# Ethernet.net
KiCad netlist of a schematic drawn in Altium Designer
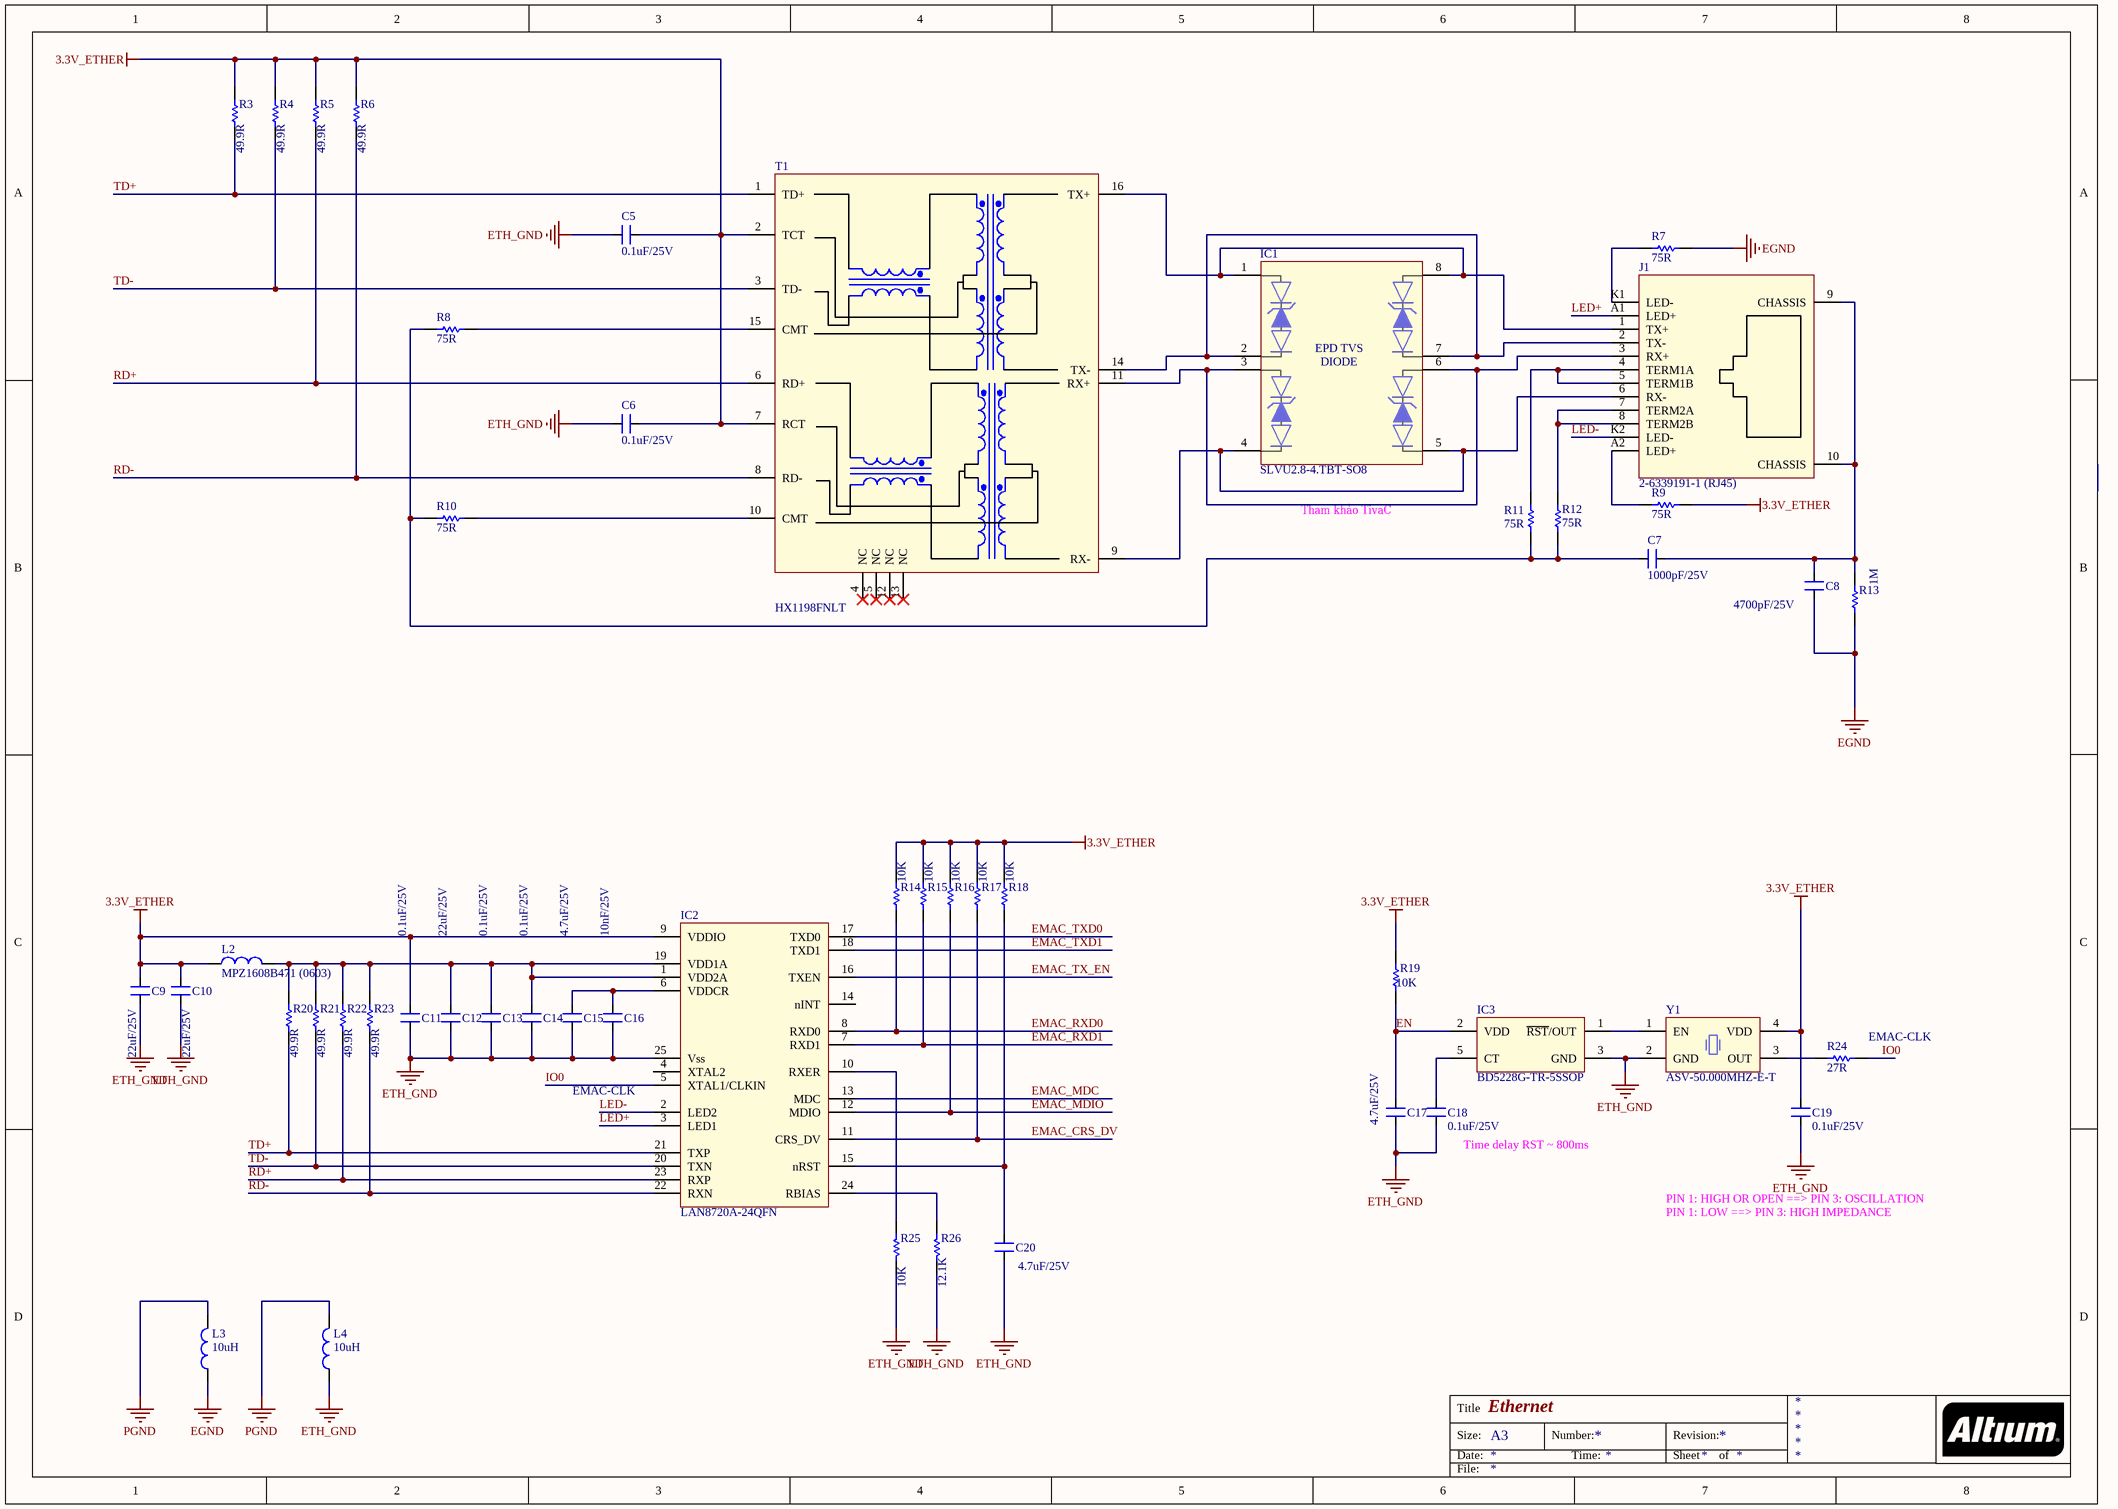
[diagram p0: Ethernet.SchDoc]

(export (version "E")
  (design (tool "Eeschema 10.0.6"))
  (components
    (comp (ref "C5")
      (value "0.1uF/25V")
      (footprint "CAP_CERA_C2012(CC0805INCH)")
      (description "0.1µF ±10% 25V Ceramic Capacitor X7R 0805 (2012 Metric)")
      (libsource (lib "lpson") (part "CAP CERA 0805"))
    )
    (comp (ref "C6")
      (value "0.1uF/25V")
      (footprint "CAP_CERA_C2012(CC0805INCH)")
      (description "0.1µF ±10% 25V Ceramic Capacitor X7R 0805 (2012 Metric)")
      (libsource (lib "lpson") (part "CAP CERA 0805"))
    )
    (comp (ref "C7")
      (value "1000pF/25V")
      (footprint "CAP_CERA_C2012(CC0805INCH)")
      (description "1000pF ±10% 25V Ceramic Capacitor X7R 0805 (2012 Metric)")
      (libsource (lib "lpson") (part "CAP CERA 0805"))
    )
    (comp (ref "C8")
      (value "4700pF/25V")
      (footprint "CAP_CERA_C2012(CC0805INCH)")
      (description "4700pF ±10% 25V Ceramic Capacitor X7R 0805 (2012 Metric)")
      (libsource (lib "lpson") (part "CAP CERA 0805"))
    )
    (comp (ref "C9")
      (value "22uF/25V")
      (footprint "CAP_CERA_C2012(CC0805INCH)")
      (description "22µF ±20% 25V Ceramic Capacitor X5R 0805 (2012 Metric)")
      (libsource (lib "lpson") (part "CAP CERA 0805"))
    )
    (comp (ref "C10")
      (value "22uF/25V")
      (footprint "CAP_CERA_C2012(CC0805INCH)")
      (description "22µF ±20% 25V Ceramic Capacitor X5R 0805 (2012 Metric)")
      (libsource (lib "lpson") (part "CAP CERA 0805"))
    )
    (comp (ref "C11")
      (value "0.1uF/25V")
      (footprint "CAP_CERA_C2012(CC0805INCH)")
      (description "0.1µF ±10% 25V Ceramic Capacitor X7R 0805 (2012 Metric)")
      (libsource (lib "lpson") (part "CAP CERA 0805"))
    )
    (comp (ref "C12")
      (value "22uF/25V")
      (footprint "CAP_CERA_C2012(CC0805INCH)")
      (description "22µF ±20% 25V Ceramic Capacitor X5R 0805 (2012 Metric)")
      (libsource (lib "lpson") (part "CAP CERA 0805"))
    )
    (comp (ref "C13")
      (value "0.1uF/25V")
      (footprint "CAP_CERA_C2012(CC0805INCH)")
      (description "0.1µF ±10% 25V Ceramic Capacitor X7R 0805 (2012 Metric)")
      (libsource (lib "lpson") (part "CAP CERA 0805"))
    )
    (comp (ref "C14")
      (value "0.1uF/25V")
      (footprint "CAP_CERA_C2012(CC0805INCH)")
      (description "0.1µF ±10% 25V Ceramic Capacitor X7R 0805 (2012 Metric)")
      (libsource (lib "lpson") (part "CAP CERA 0805"))
    )
    (comp (ref "C15")
      (value "4.7uF/25V")
      (footprint "CAP_CERA_C2012(CC0805INCH)")
      (description "4.7µF ±10% 25V Ceramic Capacitor X5R 0805 (2012 Metric)")
      (libsource (lib "lpson") (part "CAP CERA 0805"))
    )
    (comp (ref "C16")
      (value "10nF/25V")
      (footprint "CAP_CERA_C2012(CC0805INCH)")
      (description "1nF=1000pF ±10% 25V Ceramic Capacitor X7R 0805 (2012 Metric)")
      (libsource (lib "lpson") (part "CAP CERA 0805"))
    )
    (comp (ref "C17")
      (value "4.7uF/25V")
      (footprint "CAP_CERA_C2012(CC0805INCH)")
      (description "4.7µF ±10% 25V Ceramic Capacitor X5R 0805 (2012 Metric)")
      (libsource (lib "lpson") (part "CAP CERA 0805"))
    )
    (comp (ref "C18")
      (value "0.1uF/25V")
      (footprint "CAP_CERA_C2012(CC0805INCH)")
      (description "0.1µF ±10% 25V Ceramic Capacitor X7R 0805 (2012 Metric)")
      (libsource (lib "lpson") (part "CAP CERA 0805"))
    )
    (comp (ref "C19")
      (value "0.1uF/25V")
      (footprint "CAP_CERA_C2012(CC0805INCH)")
      (description "0.1µF ±10% 25V Ceramic Capacitor X7R 0805 (2012 Metric)")
      (libsource (lib "lpson") (part "CAP CERA 0805"))
    )
    (comp (ref "C20")
      (value "4.7uF/25V")
      (footprint "CAP_CERA_C2012(CC0805INCH)")
      (description "4.7µF ±10% 25V Ceramic Capacitor X5R 0805 (2012 Metric)")
      (libsource (lib "lpson") (part "CAP CERA 0805"))
    )
    (comp (ref "IC1")
      (value "SLVU2.8-4.TBT-SO8")
      (footprint "SLVU2.8-4.TBT - 8S0")
      (description "TVS DIODE 2.8V 15V 8SO, EPD TVS Diode Array For ESD and Latch-Up Protection")
      (libsource (lib "lpson") (part "SLVU2.8-4.TBT"))
    )
    (comp (ref "IC2")
      (value "LAN8720A-24QFN")
      (footprint "LAN8720A 24QFN")
      (description "IC TXRX ETHERNET 24QFN,  2/2 Transceiver Full RMII 24-QFN (4x4)")
      (libsource (lib "lpson") (part "LAN8720A-24QFN"))
    )
    (comp (ref "IC3")
      (value "BD5228G-TR-5SSOP")
      (footprint "BD5228G -5SSOP")
      (description "IC DETECTOR VOLT 2.8V ODRN 5SSOP")
      (libsource (lib "lpson") (part "BD5228G-5SSOP"))
    )
    (comp (ref "J1")
      (value "2-6339191-1 (RJ45)")
      (footprint "RJ45-A121555CT-ND")
      (description "Jack Modular Connector 8p8c (RJ45, Ethernet) 90° Angle (Right) Shielded, EMI Finger Cat5")
      (libsource (lib "lpson") (part "RJ45-2-6339191-1"))
    )
    (comp (ref "L2")
      (value "MPZ1608B471 (0603)")
      (footprint "MPZ1608B471")
      (description "FERRITE BEAD 470 OHM 0603 1LN")
      (libsource (lib "lpson") (part "L1"))
    )
    (comp (ref "L3")
      (value "10uH")
      (footprint "L/0.4")
      (description "Inductor")
      (libsource (lib "lpson") (part "L1"))
    )
    (comp (ref "L4")
      (value "10uH")
      (footprint "L/0.4")
      (description "Inductor")
      (libsource (lib "lpson") (part "L1"))
    )
    (comp (ref "R3")
      (value "49.9R")
      (footprint "Res 0805 SMD")
      (description "49.9 Ohms ±1% 0.15W Chip Resistor 0805 (2012 Metric) Military Thick Film")
      (libsource (lib "lpson") (part "RES-0805"))
    )
    (comp (ref "R4")
      (value "49.9R")
      (footprint "Res 0805 SMD")
      (description "49.9 Ohms ±1% 0.15W Chip Resistor 0805 (2012 Metric) Military Thick Film")
      (libsource (lib "lpson") (part "RES-0805"))
    )
    (comp (ref "R5")
      (value "49.9R")
      (footprint "Res 0805 SMD")
      (description "49.9 Ohms ±1% 0.15W Chip Resistor 0805 (2012 Metric) Military Thick Film")
      (libsource (lib "lpson") (part "RES-0805"))
    )
    (comp (ref "R6")
      (value "49.9R")
      (footprint "Res 0805 SMD")
      (description "49.9 Ohms ±1% 0.15W Chip Resistor 0805 (2012 Metric) Military Thick Film")
      (libsource (lib "lpson") (part "RES-0805"))
    )
    (comp (ref "R7")
      (value "75R")
      (footprint "Res 0805 SMD")
      (description "75 Ohms ±1% 0.125W, 1/8W Chip Resistor 0805 (2012 Metric) Automotive AEC-Q200 Thick Film")
      (libsource (lib "lpson") (part "RES-0805"))
    )
    (comp (ref "R8")
      (value "75R")
      (footprint "Res 0805 SMD")
      (description "75 Ohms ±1% 0.125W, 1/8W Chip Resistor 0805 (2012 Metric) Automotive AEC-Q200 Thick Film")
      (libsource (lib "lpson") (part "RES-0805"))
    )
    (comp (ref "R9")
      (value "75R")
      (footprint "Res 0805 SMD")
      (description "75 Ohms ±1% 0.125W, 1/8W Chip Resistor 0805 (2012 Metric) Automotive AEC-Q200 Thick Film")
      (libsource (lib "lpson") (part "RES-0805"))
    )
    (comp (ref "R10")
      (value "75R")
      (footprint "Res 0805 SMD")
      (description "75 Ohms ±1% 0.125W, 1/8W Chip Resistor 0805 (2012 Metric) Automotive AEC-Q200 Thick Film")
      (libsource (lib "lpson") (part "RES-0805"))
    )
    (comp (ref "R11")
      (value "75R")
      (footprint "Res 0805 SMD")
      (description "75 Ohms ±1% 0.125W, 1/8W Chip Resistor 0805 (2012 Metric) Automotive AEC-Q200 Thick Film")
      (libsource (lib "lpson") (part "RES-0805"))
    )
    (comp (ref "R12")
      (value "75R")
      (footprint "Res 0805 SMD")
      (description "75 Ohms ±1% 0.125W, 1/8W Chip Resistor 0805 (2012 Metric) Automotive AEC-Q200 Thick Film")
      (libsource (lib "lpson") (part "RES-0805"))
    )
    (comp (ref "R13")
      (value "1M")
      (footprint "Res 0805 SMD")
      (description "1 MOhms ±1% 0.125W, 1/8W Chip Resistor 0805 (2012 Metric) Automotive AEC-Q200 Thick Film")
      (libsource (lib "lpson") (part "RES-0805"))
    )
    (comp (ref "R14")
      (value "10K")
      (footprint "Res 0805 SMD")
      (description "RES SMD 249K OHM 1% 1/10W 0805")
      (fields
        (field (name "MANUFACTURER") "Yageo")
        (field (name "MANUFACTURER PART NUMBER") "RC0603FR-07249KL")
      )
      (libsource (lib "lpson") (part "RES-0805"))
    )
    (comp (ref "R15")
      (value "10K")
      (footprint "Res 0805 SMD")
      (description "RES SMD 249K OHM 1% 1/10W 0805")
      (fields
        (field (name "MANUFACTURER") "Yageo")
        (field (name "MANUFACTURER PART NUMBER") "RC0603FR-07249KL")
      )
      (libsource (lib "lpson") (part "RES-0805"))
    )
    (comp (ref "R16")
      (value "10K")
      (footprint "Res 0805 SMD")
      (description "RES SMD 249K OHM 1% 1/10W 0805")
      (fields
        (field (name "MANUFACTURER") "Yageo")
        (field (name "MANUFACTURER PART NUMBER") "RC0603FR-07249KL")
      )
      (libsource (lib "lpson") (part "RES-0805"))
    )
    (comp (ref "R17")
      (value "10K")
      (footprint "Res 0805 SMD")
      (description "RES SMD 249K OHM 1% 1/10W 0805")
      (fields
        (field (name "MANUFACTURER") "Yageo")
        (field (name "MANUFACTURER PART NUMBER") "RC0603FR-07249KL")
      )
      (libsource (lib "lpson") (part "RES-0805"))
    )
    (comp (ref "R18")
      (value "10K")
      (footprint "Res 0805 SMD")
      (description "RES SMD 249K OHM 1% 1/10W 0805")
      (fields
        (field (name "MANUFACTURER") "Yageo")
        (field (name "MANUFACTURER PART NUMBER") "RC0603FR-07249KL")
      )
      (libsource (lib "lpson") (part "RES-0805"))
    )
    (comp (ref "R19")
      (value "10K")
      (footprint "Res 0805 SMD")
      (description "RES SMD 249K OHM 1% 1/10W 0805")
      (fields
        (field (name "MANUFACTURER") "Yageo")
        (field (name "MANUFACTURER PART NUMBER") "RC0603FR-07249KL")
      )
      (libsource (lib "lpson") (part "RES-0805"))
    )
    (comp (ref "R20")
      (value "49.9R")
      (footprint "Res 0805 SMD")
      (description "49.9 Ohms ±1% 0.15W Chip Resistor 0805 (2012 Metric) Military Thick Film")
      (libsource (lib "lpson") (part "RES-0805"))
    )
    (comp (ref "R21")
      (value "49.9R")
      (footprint "Res 0805 SMD")
      (description "49.9 Ohms ±1% 0.15W Chip Resistor 0805 (2012 Metric) Military Thick Film")
      (libsource (lib "lpson") (part "RES-0805"))
    )
    (comp (ref "R22")
      (value "49.9R")
      (footprint "Res 0805 SMD")
      (description "49.9 Ohms ±1% 0.15W Chip Resistor 0805 (2012 Metric) Military Thick Film")
      (libsource (lib "lpson") (part "RES-0805"))
    )
    (comp (ref "R23")
      (value "49.9R")
      (footprint "Res 0805 SMD")
      (description "49.9 Ohms ±1% 0.15W Chip Resistor 0805 (2012 Metric) Military Thick Film")
      (libsource (lib "lpson") (part "RES-0805"))
    )
    (comp (ref "R24")
      (value "27R")
      (footprint "Res 0805 SMD")
      (description "27 Ohms ±1% 0.125W, 1/8W Chip Resistor 0805 (2012 Metric) Automotive AEC-Q200 Thick Fil")
      (libsource (lib "lpson") (part "RES-0805"))
    )
    (comp (ref "R25")
      (value "10K")
      (footprint "Res 0805 SMD")
      (description "RES SMD 249K OHM 1% 1/10W 0805")
      (fields
        (field (name "MANUFACTURER") "Yageo")
        (field (name "MANUFACTURER PART NUMBER") "RC0603FR-07249KL")
      )
      (libsource (lib "lpson") (part "RES-0805"))
    )
    (comp (ref "R26")
      (value "12.1K")
      (footprint "Res 0805 SMD")
      (description "12.1 kOhms ±1% 0.125W, 1/8W Chip Resistor 0805 (2012 Metric) Automotive AEC-Q200 Thick Film")
      (libsource (lib "lpson") (part "RES-0805"))
    )
    (comp (ref "T1")
      (value "HX1198FNLT")
      (footprint "HX1198FNL")
      (description "PULSE XFMR 1CT:1CT TX 1CT:1CT RX")
      (libsource (lib "lpson") (part "HX1198FNLT"))
    )
    (comp (ref "Y1")
      (value "ASV-50.000MHZ-E-T")
      (footprint "CR_ASV_50.000MHZ")
      (description "50MHz XO (Standard) HCMOS Oscillator 3.3V Enable/Disable 4-SMD, No Lead")
      (libsource (lib "lpson") (part "CRYSTAL_ASV"))
    )
  )
  (nets
    (net (code "1") (name "/EMAC_CRS_DV") (class "Default")
      (node (ref "IC2") (pin "11") (pinfunction "CRS_DV_11") (pintype "passive"))
      (node (ref "R17") (pin "2") (pinfunction "2_2") (pintype "passive"))
    )
    (net (code "2") (name "/EMAC_MDC") (class "Default")
      (node (ref "IC2") (pin "13") (pinfunction "MDC_13") (pintype "passive"))
    )
    (net (code "3") (name "/EMAC_MDIO") (class "Default")
      (node (ref "IC2") (pin "12") (pinfunction "MDIO_12") (pintype "passive"))
      (node (ref "R16") (pin "2") (pinfunction "2_2") (pintype "passive"))
    )
    (net (code "4") (name "/EMAC_RXD0") (class "Default")
      (node (ref "IC2") (pin "8") (pinfunction "RXD0_8") (pintype "passive"))
      (node (ref "R14") (pin "2") (pinfunction "2_2") (pintype "passive"))
    )
    (net (code "5") (name "/EMAC_RXD1") (class "Default")
      (node (ref "IC2") (pin "7") (pinfunction "RXD1_7") (pintype "passive"))
      (node (ref "R15") (pin "2") (pinfunction "2_2") (pintype "passive"))
    )
    (net (code "6") (name "/EMAC_TXD0") (class "Default")
      (node (ref "IC2") (pin "17") (pinfunction "TXD0_17") (pintype "passive"))
    )
    (net (code "7") (name "/EMAC_TXD1") (class "Default")
      (node (ref "IC2") (pin "18") (pinfunction "TXD1_18") (pintype "passive"))
    )
    (net (code "8") (name "/EMAC_TX_EN") (class "Default")
      (node (ref "IC2") (pin "16") (pinfunction "TXEN_16") (pintype "passive"))
    )
    (net (code "9") (name "/EN") (class "Default")
      (node (ref "C17") (pin "2") (pinfunction "2_2") (pintype "passive"))
      (node (ref "IC3") (pin "2") (pinfunction "VDD_2") (pintype "passive"))
      (node (ref "R19") (pin "2") (pinfunction "2_2") (pintype "passive"))
    )
    (net (code "10") (name "/IO0") (class "Default")
      (node (ref "IC2") (pin "5") (pinfunction "XTAL1/CLKIN_5") (pintype "passive"))
      (node (ref "R24") (pin "2") (pinfunction "2_2") (pintype "passive"))
    )
    (net (code "11") (name "/LED+") (class "Default")
      (node (ref "IC2") (pin "3") (pinfunction "LED1_3") (pintype "passive"))
      (node (ref "J1") (pin "A1") (pinfunction "LED+_A1") (pintype "passive"))
    )
    (net (code "12") (name "/LED-") (class "Default")
      (node (ref "IC2") (pin "2") (pinfunction "LED2_2") (pintype "passive"))
      (node (ref "J1") (pin "K2") (pinfunction "LED-_K2") (pintype "passive"))
    )
    (net (code "13") (name "/RD+") (class "Default")
      (node (ref "IC2") (pin "23") (pinfunction "RXP_23") (pintype "passive"))
      (node (ref "R22") (pin "1") (pinfunction "1_1") (pintype "passive"))
      (node (ref "R5") (pin "2") (pinfunction "2_2") (pintype "passive"))
      (node (ref "T1") (pin "6") (pinfunction "RD+_6") (pintype "passive"))
    )
    (net (code "14") (name "/RD-") (class "Default")
      (node (ref "IC2") (pin "22") (pinfunction "RXN_22") (pintype "passive"))
      (node (ref "R23") (pin "1") (pinfunction "1_1") (pintype "passive"))
      (node (ref "R6") (pin "2") (pinfunction "2_2") (pintype "passive"))
      (node (ref "T1") (pin "8") (pinfunction "RD-_8") (pintype "passive"))
    )
    (net (code "15") (name "/TD+") (class "Default")
      (node (ref "IC2") (pin "21") (pinfunction "TXP_21") (pintype "passive"))
      (node (ref "R20") (pin "1") (pinfunction "1_1") (pintype "passive"))
      (node (ref "R3") (pin "2") (pinfunction "2_2") (pintype "passive"))
      (node (ref "T1") (pin "1") (pinfunction "TD+_1") (pintype "passive"))
    )
    (net (code "16") (name "/TD-") (class "Default")
      (node (ref "IC2") (pin "20") (pinfunction "TXN_20") (pintype "passive"))
      (node (ref "R21") (pin "1") (pinfunction "1_1") (pintype "passive"))
      (node (ref "R4") (pin "2") (pinfunction "2_2") (pintype "passive"))
      (node (ref "T1") (pin "3") (pinfunction "TD-_3") (pintype "passive"))
    )
    (net (code "17") (name "3.3V_ETHER") (class "Default")
      (node (ref "C10") (pin "2") (pinfunction "2_2") (pintype "passive"))
      (node (ref "C11") (pin "2") (pinfunction "2_2") (pintype "passive"))
      (node (ref "C19") (pin "2") (pinfunction "2_2") (pintype "passive"))
      (node (ref "C5") (pin "1") (pinfunction "1_1") (pintype "passive"))
      (node (ref "C6") (pin "1") (pinfunction "1_1") (pintype "passive"))
      (node (ref "C9") (pin "2") (pinfunction "2_2") (pintype "passive"))
      (node (ref "IC2") (pin "9") (pinfunction "VDDIO_9") (pintype "passive"))
      (node (ref "L2") (pin "1") (pinfunction "1_1") (pintype "passive"))
      (node (ref "R14") (pin "1") (pinfunction "1_1") (pintype "passive"))
      (node (ref "R15") (pin "1") (pinfunction "1_1") (pintype "passive"))
      (node (ref "R16") (pin "1") (pinfunction "1_1") (pintype "passive"))
      (node (ref "R17") (pin "1") (pinfunction "1_1") (pintype "passive"))
      (node (ref "R18") (pin "1") (pinfunction "1_1") (pintype "passive"))
      (node (ref "R19") (pin "1") (pinfunction "1_1") (pintype "passive"))
      (node (ref "R3") (pin "1") (pinfunction "1_1") (pintype "passive"))
      (node (ref "R4") (pin "1") (pinfunction "1_1") (pintype "passive"))
      (node (ref "R5") (pin "1") (pinfunction "1_1") (pintype "passive"))
      (node (ref "R6") (pin "1") (pinfunction "1_1") (pintype "passive"))
      (node (ref "R9") (pin "1") (pinfunction "1_1") (pintype "passive"))
      (node (ref "T1") (pin "2") (pinfunction "TCT_2") (pintype "passive"))
      (node (ref "T1") (pin "7") (pinfunction "RCT_7") (pintype "passive"))
      (node (ref "Y1") (pin "4") (pinfunction "VDD_4") (pintype "passive"))
    )
    (net (code "18") (name "EGND") (class "Default")
      (node (ref "C8") (pin "2") (pinfunction "2_2") (pintype "passive"))
      (node (ref "L3") (pin "1") (pinfunction "1_1") (pintype "passive"))
      (node (ref "R13") (pin "1") (pinfunction "1_1") (pintype "passive"))
      (node (ref "R7") (pin "1") (pinfunction "1_1") (pintype "passive"))
    )
    (net (code "19") (name "ETH_GND") (class "Default")
      (node (ref "C10") (pin "1") (pinfunction "1_1") (pintype "passive"))
      (node (ref "C11") (pin "1") (pinfunction "1_1") (pintype "passive"))
      (node (ref "C12") (pin "1") (pinfunction "1_1") (pintype "passive"))
      (node (ref "C13") (pin "1") (pinfunction "1_1") (pintype "passive"))
      (node (ref "C14") (pin "1") (pinfunction "1_1") (pintype "passive"))
      (node (ref "C15") (pin "1") (pinfunction "1_1") (pintype "passive"))
      (node (ref "C16") (pin "1") (pinfunction "1_1") (pintype "passive"))
      (node (ref "C17") (pin "1") (pinfunction "1_1") (pintype "passive"))
      (node (ref "C18") (pin "1") (pinfunction "1_1") (pintype "passive"))
      (node (ref "C19") (pin "1") (pinfunction "1_1") (pintype "passive"))
      (node (ref "C20") (pin "1") (pinfunction "1_1") (pintype "passive"))
      (node (ref "C5") (pin "2") (pinfunction "2_2") (pintype "passive"))
      (node (ref "C6") (pin "2") (pinfunction "2_2") (pintype "passive"))
      (node (ref "C9") (pin "1") (pinfunction "1_1") (pintype "passive"))
      (node (ref "IC2") (pin "25") (pinfunction "Vss_25") (pintype "passive"))
      (node (ref "IC3") (pin "3") (pinfunction "GND_3") (pintype "passive"))
      (node (ref "L4") (pin "1") (pinfunction "1_1") (pintype "passive"))
      (node (ref "R25") (pin "2") (pinfunction "2_2") (pintype "passive"))
      (node (ref "R26") (pin "2") (pinfunction "2_2") (pintype "passive"))
      (node (ref "Y1") (pin "2") (pinfunction "GND_2") (pintype "passive"))
    )
    (net (code "20") (name "Net-(C7-Pad1)") (class "Default")
      (node (ref "C7") (pin "1") (pinfunction "1_1") (pintype "passive"))
      (node (ref "C8") (pin "1") (pinfunction "1_1") (pintype "passive"))
      (node (ref "J1") (pin "10") (pinfunction "CHASSIS_10") (pintype "passive"))
      (node (ref "J1") (pin "9") (pinfunction "CHASSIS_9") (pintype "passive"))
      (node (ref "R13") (pin "2") (pinfunction "2_2") (pintype "passive"))
    )
    (net (code "21") (name "Net-(C7-Pad2)") (class "Default")
      (node (ref "C7") (pin "2") (pinfunction "2_2") (pintype "passive"))
      (node (ref "R10") (pin "2") (pinfunction "2_2") (pintype "passive"))
      (node (ref "R11") (pin "1") (pinfunction "1_1") (pintype "passive"))
      (node (ref "R12") (pin "1") (pinfunction "1_1") (pintype "passive"))
      (node (ref "R8") (pin "2") (pinfunction "2_2") (pintype "passive"))
    )
    (net (code "22") (name "Net-(IC2-RBIAS)") (class "Default")
      (node (ref "IC2") (pin "24") (pinfunction "RBIAS_24") (pintype "passive"))
      (node (ref "R26") (pin "1") (pinfunction "1_1") (pintype "passive"))
    )
    (net (code "23") (name "Net-(IC2-RXER)") (class "Default")
      (node (ref "IC2") (pin "10") (pinfunction "RXER_10") (pintype "passive"))
      (node (ref "R25") (pin "1") (pinfunction "1_1") (pintype "passive"))
    )
    (net (code "24") (name "Net-(IC2-VDD1A)") (class "Default")
      (node (ref "C12") (pin "2") (pinfunction "2_2") (pintype "passive"))
      (node (ref "C13") (pin "2") (pinfunction "2_2") (pintype "passive"))
      (node (ref "C14") (pin "2") (pinfunction "2_2") (pintype "passive"))
      (node (ref "IC2") (pin "1") (pinfunction "VDD2A_1") (pintype "passive"))
      (node (ref "IC2") (pin "19") (pinfunction "VDD1A_19") (pintype "passive"))
      (node (ref "L2") (pin "2") (pinfunction "2_2") (pintype "passive"))
      (node (ref "R20") (pin "2") (pinfunction "2_2") (pintype "passive"))
      (node (ref "R21") (pin "2") (pinfunction "2_2") (pintype "passive"))
      (node (ref "R22") (pin "2") (pinfunction "2_2") (pintype "passive"))
      (node (ref "R23") (pin "2") (pinfunction "2_2") (pintype "passive"))
    )
    (net (code "25") (name "Net-(IC2-VDDCR)") (class "Default")
      (node (ref "C15") (pin "2") (pinfunction "2_2") (pintype "passive"))
      (node (ref "C16") (pin "2") (pinfunction "2_2") (pintype "passive"))
      (node (ref "IC2") (pin "6") (pinfunction "VDDCR_6") (pintype "passive"))
    )
    (net (code "26") (name "Net-(IC2-nRST)") (class "Default")
      (node (ref "C20") (pin "2") (pinfunction "2_2") (pintype "passive"))
      (node (ref "IC2") (pin "15") (pinfunction "nRST_15") (pintype "passive"))
      (node (ref "R18") (pin "2") (pinfunction "2_2") (pintype "passive"))
    )
    (net (code "27") (name "Net-(IC3-CT)") (class "Default")
      (node (ref "C18") (pin "2") (pinfunction "2_2") (pintype "passive"))
      (node (ref "IC3") (pin "5") (pinfunction "CT_5") (pintype "passive"))
    )
    (net (code "28") (name "Net-(IC3-~{RST}{slash}OUT)") (class "Default")
      (node (ref "IC3") (pin "1") (pinfunction "~{RST}/OUT_1") (pintype "passive"))
      (node (ref "Y1") (pin "1") (pinfunction "EN_1") (pintype "passive"))
    )
    (net (code "29") (name "Net-(J1-LED+-PadA2)") (class "Default")
      (node (ref "J1") (pin "A2") (pinfunction "LED+_A2") (pintype "passive"))
      (node (ref "R9") (pin "2") (pinfunction "2_2") (pintype "passive"))
    )
    (net (code "30") (name "Net-(J1-LED--PadK1)") (class "Default")
      (node (ref "J1") (pin "K1") (pinfunction "LED-_K1") (pintype "passive"))
      (node (ref "R7") (pin "2") (pinfunction "2_2") (pintype "passive"))
    )
    (net (code "31") (name "Net-(J1-RX+)") (class "Default")
      (node (ref "IC1") (pin "3") (pinfunction "A1_3") (pintype "passive"))
      (node (ref "IC1") (pin "6") (pinfunction "A1_6") (pintype "passive"))
      (node (ref "J1") (pin "3") (pinfunction "RX+_3") (pintype "passive"))
      (node (ref "T1") (pin "11") (pinfunction "RX+_11") (pintype "passive"))
    )
    (net (code "32") (name "Net-(J1-RX-)") (class "Default")
      (node (ref "IC1") (pin "4") (pinfunction "K1_4") (pintype "passive"))
      (node (ref "IC1") (pin "5") (pinfunction "K1_5") (pintype "passive"))
      (node (ref "J1") (pin "6") (pinfunction "RX-_6") (pintype "passive"))
      (node (ref "T1") (pin "9") (pinfunction "RX-_9") (pintype "passive"))
    )
    (net (code "33") (name "Net-(J1-TERM1A)") (class "Default")
      (node (ref "J1") (pin "4") (pinfunction "TERM1A_4") (pintype "passive"))
      (node (ref "J1") (pin "5") (pinfunction "TERM1B_5") (pintype "passive"))
      (node (ref "R11") (pin "2") (pinfunction "2_2") (pintype "passive"))
    )
    (net (code "34") (name "Net-(J1-TERM2A)") (class "Default")
      (node (ref "J1") (pin "7") (pinfunction "TERM2A_7") (pintype "passive"))
      (node (ref "J1") (pin "8") (pinfunction "TERM2B_8") (pintype "passive"))
      (node (ref "R12") (pin "2") (pinfunction "2_2") (pintype "passive"))
    )
    (net (code "35") (name "Net-(J1-TX+)") (class "Default")
      (node (ref "IC1") (pin "1") (pinfunction "A1_1") (pintype "passive"))
      (node (ref "IC1") (pin "8") (pinfunction "A1_8") (pintype "passive"))
      (node (ref "J1") (pin "1") (pinfunction "TX+_1") (pintype "passive"))
      (node (ref "T1") (pin "16") (pinfunction "TX+_16") (pintype "passive"))
    )
    (net (code "36") (name "Net-(J1-TX-)") (class "Default")
      (node (ref "IC1") (pin "2") (pinfunction "K1_2") (pintype "passive"))
      (node (ref "IC1") (pin "7") (pinfunction "K1_7") (pintype "passive"))
      (node (ref "J1") (pin "2") (pinfunction "TX-_2") (pintype "passive"))
      (node (ref "T1") (pin "14") (pinfunction "TX-_14") (pintype "passive"))
    )
    (net (code "37") (name "Net-(R8-Pad1)") (class "Default")
      (node (ref "R8") (pin "1") (pinfunction "1_1") (pintype "passive"))
      (node (ref "T1") (pin "15") (pinfunction "CMT_15") (pintype "passive"))
    )
    (net (code "38") (name "Net-(R10-Pad1)") (class "Default")
      (node (ref "R10") (pin "1") (pinfunction "1_1") (pintype "passive"))
      (node (ref "T1") (pin "10") (pinfunction "CMT_10") (pintype "passive"))
    )
    (net (code "39") (name "Net-(Y1-OUT)") (class "Default")
      (node (ref "R24") (pin "1") (pinfunction "1_1") (pintype "passive"))
      (node (ref "Y1") (pin "3") (pinfunction "OUT_3") (pintype "passive"))
    )
    (net (code "40") (name "PGND") (class "Default")
      (node (ref "L3") (pin "2") (pinfunction "2_2") (pintype "passive"))
      (node (ref "L4") (pin "2") (pinfunction "2_2") (pintype "passive"))
    )
    (net (code "41") (name "unconnected-(IC2-XTAL2-Pad4)") (class "Default")
      (node (ref "IC2") (pin "4") (pinfunction "XTAL2_4") (pintype "passive"))
    )
    (net (code "42") (name "unconnected-(IC2-nINT-Pad14)") (class "Default")
      (node (ref "IC2") (pin "14") (pinfunction "nINT_14") (pintype "passive"))
    )
    (net (code "43") (name "unconnected-(T1-NC-Pad4)") (class "Default")
      (node (ref "T1") (pin "4") (pinfunction "NC_4") (pintype "passive+no_connect"))
    )
    (net (code "44") (name "unconnected-(T1-NC-Pad5)") (class "Default")
      (node (ref "T1") (pin "5") (pinfunction "NC_5") (pintype "passive+no_connect"))
    )
    (net (code "45") (name "unconnected-(T1-NC-Pad12)") (class "Default")
      (node (ref "T1") (pin "12") (pinfunction "NC_12") (pintype "passive+no_connect"))
    )
    (net (code "46") (name "unconnected-(T1-NC-Pad13)") (class "Default")
      (node (ref "T1") (pin "13") (pinfunction "NC_13") (pintype "passive+no_connect"))
    )
  )
)
